# nibblet.net
KiCad netlist of a schematic drawn in EAGLE
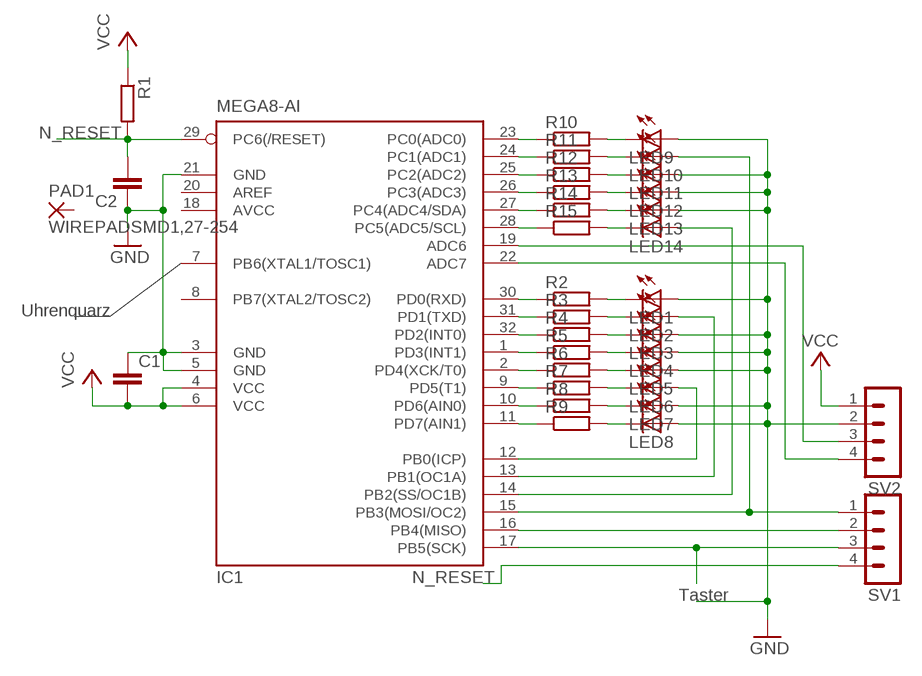
[diagram p0: schematic, sheet 1]

(export (version "E")
  (design (tool "Eeschema 10.0.6"))
  (components
    (comp (ref "C1")
      (value "C-EUC1206")
      (footprint "eagle-import:C1206")
      (libsource (lib "eagle-import") (part "C-EUC1206"))
    )
    (comp (ref "C2")
      (value "C-EUC1206")
      (footprint "eagle-import:C1206")
      (libsource (lib "eagle-import") (part "C-EUC1206"))
    )
    (comp (ref "IC1")
      (value "MEGA8-AI")
      (footprint "eagle-import:TQFP32-08")
      (libsource (lib "eagle-import") (part "MEGA8-AI"))
    )
    (comp (ref "LED1")
      (value "LEDCHIP-LED0805")
      (footprint "eagle-import:CHIP-LED0805")
      (libsource (lib "eagle-import") (part "LEDCHIP-LED0805"))
    )
    (comp (ref "LED2")
      (value "LEDCHIP-LED0805")
      (footprint "eagle-import:CHIP-LED0805")
      (libsource (lib "eagle-import") (part "LEDCHIP-LED0805"))
    )
    (comp (ref "LED3")
      (value "LEDCHIP-LED0805")
      (footprint "eagle-import:CHIP-LED0805")
      (libsource (lib "eagle-import") (part "LEDCHIP-LED0805"))
    )
    (comp (ref "LED4")
      (value "LEDCHIP-LED0805")
      (footprint "eagle-import:CHIP-LED0805")
      (libsource (lib "eagle-import") (part "LEDCHIP-LED0805"))
    )
    (comp (ref "LED5")
      (value "LEDCHIP-LED0805")
      (footprint "eagle-import:CHIP-LED0805")
      (libsource (lib "eagle-import") (part "LEDCHIP-LED0805"))
    )
    (comp (ref "LED6")
      (value "LEDCHIP-LED0805")
      (footprint "eagle-import:CHIP-LED0805")
      (libsource (lib "eagle-import") (part "LEDCHIP-LED0805"))
    )
    (comp (ref "LED7")
      (value "LEDCHIP-LED0805")
      (footprint "eagle-import:CHIP-LED0805")
      (libsource (lib "eagle-import") (part "LEDCHIP-LED0805"))
    )
    (comp (ref "LED8")
      (value "LEDCHIP-LED0805")
      (footprint "eagle-import:CHIP-LED0805")
      (libsource (lib "eagle-import") (part "LEDCHIP-LED0805"))
    )
    (comp (ref "LED9")
      (value "LEDCHIP-LED0805")
      (footprint "eagle-import:CHIP-LED0805")
      (libsource (lib "eagle-import") (part "LEDCHIP-LED0805"))
    )
    (comp (ref "LED10")
      (value "LEDCHIP-LED0805")
      (footprint "eagle-import:CHIP-LED0805")
      (libsource (lib "eagle-import") (part "LEDCHIP-LED0805"))
    )
    (comp (ref "LED11")
      (value "LEDCHIP-LED0805")
      (footprint "eagle-import:CHIP-LED0805")
      (libsource (lib "eagle-import") (part "LEDCHIP-LED0805"))
    )
    (comp (ref "LED12")
      (value "LEDCHIP-LED0805")
      (footprint "eagle-import:CHIP-LED0805")
      (libsource (lib "eagle-import") (part "LEDCHIP-LED0805"))
    )
    (comp (ref "LED13")
      (value "LEDCHIP-LED0805")
      (footprint "eagle-import:CHIP-LED0805")
      (libsource (lib "eagle-import") (part "LEDCHIP-LED0805"))
    )
    (comp (ref "LED14")
      (value "LEDCHIP-LED0805")
      (footprint "eagle-import:CHIP-LED0805")
      (libsource (lib "eagle-import") (part "LEDCHIP-LED0805"))
    )
    (comp (ref "PAD1")
      (value "WIREPADSMD1,27-254")
      (footprint "eagle-import:SMD1,27-2,54")
      (libsource (lib "eagle-import") (part "WIREPADSMD1,27-254"))
    )
    (comp (ref "R1")
      (value "R-EU_M1206")
      (footprint "eagle-import:M1206")
      (libsource (lib "eagle-import") (part "R-EU_M1206"))
    )
    (comp (ref "R2")
      (value "R-EU_R0805")
      (footprint "eagle-import:R0805")
      (libsource (lib "eagle-import") (part "R-EU_R0805"))
    )
    (comp (ref "R3")
      (value "R-EU_R0805")
      (footprint "eagle-import:R0805")
      (libsource (lib "eagle-import") (part "R-EU_R0805"))
    )
    (comp (ref "R4")
      (value "R-EU_R0805")
      (footprint "eagle-import:R0805")
      (libsource (lib "eagle-import") (part "R-EU_R0805"))
    )
    (comp (ref "R5")
      (value "R-EU_R0805")
      (footprint "eagle-import:R0805")
      (libsource (lib "eagle-import") (part "R-EU_R0805"))
    )
    (comp (ref "R6")
      (value "R-EU_R0805")
      (footprint "eagle-import:R0805")
      (libsource (lib "eagle-import") (part "R-EU_R0805"))
    )
    (comp (ref "R7")
      (value "R-EU_R0805")
      (footprint "eagle-import:R0805")
      (libsource (lib "eagle-import") (part "R-EU_R0805"))
    )
    (comp (ref "R8")
      (value "R-EU_R0805")
      (footprint "eagle-import:R0805")
      (libsource (lib "eagle-import") (part "R-EU_R0805"))
    )
    (comp (ref "R9")
      (value "R-EU_R0805")
      (footprint "eagle-import:R0805")
      (libsource (lib "eagle-import") (part "R-EU_R0805"))
    )
    (comp (ref "R10")
      (value "R-EU_R0805")
      (footprint "eagle-import:R0805")
      (libsource (lib "eagle-import") (part "R-EU_R0805"))
    )
    (comp (ref "R11")
      (value "R-EU_R0805")
      (footprint "eagle-import:R0805")
      (libsource (lib "eagle-import") (part "R-EU_R0805"))
    )
    (comp (ref "R12")
      (value "R-EU_R0805")
      (footprint "eagle-import:R0805")
      (libsource (lib "eagle-import") (part "R-EU_R0805"))
    )
    (comp (ref "R13")
      (value "R-EU_R0805")
      (footprint "eagle-import:R0805")
      (libsource (lib "eagle-import") (part "R-EU_R0805"))
    )
    (comp (ref "R14")
      (value "R-EU_R0805")
      (footprint "eagle-import:R0805")
      (libsource (lib "eagle-import") (part "R-EU_R0805"))
    )
    (comp (ref "R15")
      (value "R-EU_R0805")
      (footprint "eagle-import:R0805")
      (libsource (lib "eagle-import") (part "R-EU_R0805"))
    )
    (comp (ref "SV1")
      (value "MA04-1")
      (footprint "eagle-import:MA04-1")
      (libsource (lib "eagle-import") (part "MA04-1"))
    )
    (comp (ref "SV2")
      (value "MA04-1")
      (footprint "eagle-import:MA04-1")
      (libsource (lib "eagle-import") (part "MA04-1"))
    )
  )
  (nets
    (net (code "1") (name "/AVCC") (class "Default")
      (node (ref "IC1") (pin "18") (pinfunction "AVCC_18") (pintype "power_in"))
    )
    (net (code "2") (name "/N_RESET") (class "Default")
      (node (ref "C2") (pin "2") (pinfunction "2_2") (pintype "passive"))
      (node (ref "IC1") (pin "29") (pinfunction "PC6(/RESET)_29") (pintype "bidirectional"))
      (node (ref "R1") (pin "2") (pinfunction "2_2") (pintype "passive"))
      (node (ref "SV1") (pin "4") (pinfunction "4_4") (pintype "passive"))
    )
    (net (code "3") (name "GND") (class "Default")
      (node (ref "C1") (pin "1") (pinfunction "1_1") (pintype "passive"))
      (node (ref "C2") (pin "1") (pinfunction "1_1") (pintype "passive"))
      (node (ref "IC1") (pin "21") (pinfunction "GND_21") (pintype "power_in"))
      (node (ref "IC1") (pin "3") (pinfunction "GND_3") (pintype "power_in"))
      (node (ref "IC1") (pin "5") (pinfunction "GND_5") (pintype "power_in"))
      (node (ref "LED1") (pin "A") (pinfunction "A_A") (pintype "passive"))
      (node (ref "LED11") (pin "A") (pinfunction "A_A") (pintype "passive"))
      (node (ref "LED12") (pin "A") (pinfunction "A_A") (pintype "passive"))
      (node (ref "LED13") (pin "A") (pinfunction "A_A") (pintype "passive"))
      (node (ref "LED3") (pin "A") (pinfunction "A_A") (pintype "passive"))
      (node (ref "LED4") (pin "A") (pinfunction "A_A") (pintype "passive"))
      (node (ref "LED5") (pin "A") (pinfunction "A_A") (pintype "passive"))
      (node (ref "LED7") (pin "A") (pinfunction "A_A") (pintype "passive"))
      (node (ref "LED8") (pin "A") (pinfunction "A_A") (pintype "passive"))
      (node (ref "LED9") (pin "A") (pinfunction "A_A") (pintype "passive"))
      (node (ref "SV2") (pin "2") (pinfunction "2_2") (pintype "passive"))
    )
    (net (code "4") (name "Net-(IC1-ADC6)") (class "Default")
      (node (ref "IC1") (pin "19") (pinfunction "ADC6_19") (pintype "bidirectional"))
      (node (ref "SV2") (pin "3") (pinfunction "3_3") (pintype "passive"))
    )
    (net (code "5") (name "Net-(IC1-ADC7)") (class "Default")
      (node (ref "IC1") (pin "22") (pinfunction "ADC7_22") (pintype "bidirectional"))
      (node (ref "SV2") (pin "4") (pinfunction "4_4") (pintype "passive"))
    )
    (net (code "6") (name "Net-(IC1-PB0(ICP))") (class "Default")
      (node (ref "IC1") (pin "12") (pinfunction "PB0(ICP)_12") (pintype "bidirectional"))
      (node (ref "LED6") (pin "A") (pinfunction "A_A") (pintype "passive"))
    )
    (net (code "7") (name "Net-(IC1-PB1(OC1A))") (class "Default")
      (node (ref "IC1") (pin "13") (pinfunction "PB1(OC1A)_13") (pintype "bidirectional"))
      (node (ref "LED2") (pin "A") (pinfunction "A_A") (pintype "passive"))
    )
    (net (code "8") (name "Net-(IC1-PB2(SS{slash}OC1B))") (class "Default")
      (node (ref "IC1") (pin "14") (pinfunction "PB2(SS/OC1B)_14") (pintype "bidirectional"))
      (node (ref "LED14") (pin "A") (pinfunction "A_A") (pintype "passive"))
    )
    (net (code "9") (name "Net-(IC1-PB3(MOSI{slash}OC2))") (class "Default")
      (node (ref "IC1") (pin "15") (pinfunction "PB3(MOSI/OC2)_15") (pintype "bidirectional"))
      (node (ref "LED10") (pin "A") (pinfunction "A_A") (pintype "passive"))
      (node (ref "SV1") (pin "1") (pinfunction "1_1") (pintype "passive"))
    )
    (net (code "10") (name "Net-(IC1-PB4(MISO))") (class "Default")
      (node (ref "IC1") (pin "16") (pinfunction "PB4(MISO)_16") (pintype "bidirectional"))
      (node (ref "SV1") (pin "2") (pinfunction "2_2") (pintype "passive"))
    )
    (net (code "11") (name "Net-(IC1-PB5(SCK))") (class "Default")
      (node (ref "IC1") (pin "17") (pinfunction "PB5(SCK)_17") (pintype "bidirectional"))
      (node (ref "SV1") (pin "3") (pinfunction "3_3") (pintype "passive"))
    )
    (net (code "12") (name "Net-(IC1-PC0(ADC0))") (class "Default")
      (node (ref "IC1") (pin "23") (pinfunction "PC0(ADC0)_23") (pintype "bidirectional"))
      (node (ref "R10") (pin "1") (pinfunction "1_1") (pintype "passive"))
    )
    (net (code "13") (name "Net-(IC1-PC1(ADC1))") (class "Default")
      (node (ref "IC1") (pin "24") (pinfunction "PC1(ADC1)_24") (pintype "bidirectional"))
      (node (ref "R11") (pin "1") (pinfunction "1_1") (pintype "passive"))
    )
    (net (code "14") (name "Net-(IC1-PC2(ADC2))") (class "Default")
      (node (ref "IC1") (pin "25") (pinfunction "PC2(ADC2)_25") (pintype "bidirectional"))
      (node (ref "R12") (pin "1") (pinfunction "1_1") (pintype "passive"))
    )
    (net (code "15") (name "Net-(IC1-PC3(ADC3))") (class "Default")
      (node (ref "IC1") (pin "26") (pinfunction "PC3(ADC3)_26") (pintype "bidirectional"))
      (node (ref "R13") (pin "1") (pinfunction "1_1") (pintype "passive"))
    )
    (net (code "16") (name "Net-(IC1-PC4(ADC4{slash}SDA))") (class "Default")
      (node (ref "IC1") (pin "27") (pinfunction "PC4(ADC4/SDA)_27") (pintype "bidirectional"))
      (node (ref "R14") (pin "1") (pinfunction "1_1") (pintype "passive"))
    )
    (net (code "17") (name "Net-(IC1-PC5(ADC5{slash}SCL))") (class "Default")
      (node (ref "IC1") (pin "28") (pinfunction "PC5(ADC5/SCL)_28") (pintype "bidirectional"))
      (node (ref "R15") (pin "1") (pinfunction "1_1") (pintype "passive"))
    )
    (net (code "18") (name "Net-(IC1-PD0(RXD))") (class "Default")
      (node (ref "IC1") (pin "30") (pinfunction "PD0(RXD)_30") (pintype "bidirectional"))
      (node (ref "R2") (pin "1") (pinfunction "1_1") (pintype "passive"))
    )
    (net (code "19") (name "Net-(IC1-PD1(TXD))") (class "Default")
      (node (ref "IC1") (pin "31") (pinfunction "PD1(TXD)_31") (pintype "bidirectional"))
      (node (ref "R3") (pin "1") (pinfunction "1_1") (pintype "passive"))
    )
    (net (code "20") (name "Net-(IC1-PD2(INT0))") (class "Default")
      (node (ref "IC1") (pin "32") (pinfunction "PD2(INT0)_32") (pintype "bidirectional"))
      (node (ref "R4") (pin "1") (pinfunction "1_1") (pintype "passive"))
    )
    (net (code "21") (name "Net-(IC1-PD3(INT1))") (class "Default")
      (node (ref "IC1") (pin "1") (pinfunction "PD3(INT1)_1") (pintype "bidirectional"))
      (node (ref "R5") (pin "1") (pinfunction "1_1") (pintype "passive"))
    )
    (net (code "22") (name "Net-(IC1-PD4(XCK{slash}T0))") (class "Default")
      (node (ref "IC1") (pin "2") (pinfunction "PD4(XCK/T0)_2") (pintype "bidirectional"))
      (node (ref "R6") (pin "1") (pinfunction "1_1") (pintype "passive"))
    )
    (net (code "23") (name "Net-(IC1-PD5(T1))") (class "Default")
      (node (ref "IC1") (pin "9") (pinfunction "PD5(T1)_9") (pintype "bidirectional"))
      (node (ref "R7") (pin "1") (pinfunction "1_1") (pintype "passive"))
    )
    (net (code "24") (name "Net-(IC1-PD6(AIN0))") (class "Default")
      (node (ref "IC1") (pin "10") (pinfunction "PD6(AIN0)_10") (pintype "bidirectional"))
      (node (ref "R8") (pin "1") (pinfunction "1_1") (pintype "passive"))
    )
    (net (code "25") (name "Net-(IC1-PD7(AIN1))") (class "Default")
      (node (ref "IC1") (pin "11") (pinfunction "PD7(AIN1)_11") (pintype "bidirectional"))
      (node (ref "R9") (pin "1") (pinfunction "1_1") (pintype "passive"))
    )
    (net (code "26") (name "Net-(LED1-PadC)") (class "Default")
      (node (ref "LED1") (pin "C") (pinfunction "C_C") (pintype "passive"))
      (node (ref "R2") (pin "2") (pinfunction "2_2") (pintype "passive"))
    )
    (net (code "27") (name "Net-(LED2-PadC)") (class "Default")
      (node (ref "LED2") (pin "C") (pinfunction "C_C") (pintype "passive"))
      (node (ref "R3") (pin "2") (pinfunction "2_2") (pintype "passive"))
    )
    (net (code "28") (name "Net-(LED3-PadC)") (class "Default")
      (node (ref "LED3") (pin "C") (pinfunction "C_C") (pintype "passive"))
      (node (ref "R4") (pin "2") (pinfunction "2_2") (pintype "passive"))
    )
    (net (code "29") (name "Net-(LED4-PadC)") (class "Default")
      (node (ref "LED4") (pin "C") (pinfunction "C_C") (pintype "passive"))
      (node (ref "R5") (pin "2") (pinfunction "2_2") (pintype "passive"))
    )
    (net (code "30") (name "Net-(LED5-PadC)") (class "Default")
      (node (ref "LED5") (pin "C") (pinfunction "C_C") (pintype "passive"))
      (node (ref "R6") (pin "2") (pinfunction "2_2") (pintype "passive"))
    )
    (net (code "31") (name "Net-(LED6-PadC)") (class "Default")
      (node (ref "LED6") (pin "C") (pinfunction "C_C") (pintype "passive"))
      (node (ref "R7") (pin "2") (pinfunction "2_2") (pintype "passive"))
    )
    (net (code "32") (name "Net-(LED7-PadC)") (class "Default")
      (node (ref "LED7") (pin "C") (pinfunction "C_C") (pintype "passive"))
      (node (ref "R8") (pin "2") (pinfunction "2_2") (pintype "passive"))
    )
    (net (code "33") (name "Net-(LED8-PadC)") (class "Default")
      (node (ref "LED8") (pin "C") (pinfunction "C_C") (pintype "passive"))
      (node (ref "R9") (pin "2") (pinfunction "2_2") (pintype "passive"))
    )
    (net (code "34") (name "Net-(LED9-PadC)") (class "Default")
      (node (ref "LED9") (pin "C") (pinfunction "C_C") (pintype "passive"))
      (node (ref "R10") (pin "2") (pinfunction "2_2") (pintype "passive"))
    )
    (net (code "35") (name "Net-(LED10-PadC)") (class "Default")
      (node (ref "LED10") (pin "C") (pinfunction "C_C") (pintype "passive"))
      (node (ref "R11") (pin "2") (pinfunction "2_2") (pintype "passive"))
    )
    (net (code "36") (name "Net-(LED11-PadC)") (class "Default")
      (node (ref "LED11") (pin "C") (pinfunction "C_C") (pintype "passive"))
      (node (ref "R12") (pin "2") (pinfunction "2_2") (pintype "passive"))
    )
    (net (code "37") (name "Net-(LED12-PadC)") (class "Default")
      (node (ref "LED12") (pin "C") (pinfunction "C_C") (pintype "passive"))
      (node (ref "R13") (pin "2") (pinfunction "2_2") (pintype "passive"))
    )
    (net (code "38") (name "Net-(LED13-PadC)") (class "Default")
      (node (ref "LED13") (pin "C") (pinfunction "C_C") (pintype "passive"))
      (node (ref "R14") (pin "2") (pinfunction "2_2") (pintype "passive"))
    )
    (net (code "39") (name "Net-(LED14-PadC)") (class "Default")
      (node (ref "LED14") (pin "C") (pinfunction "C_C") (pintype "passive"))
      (node (ref "R15") (pin "2") (pinfunction "2_2") (pintype "passive"))
    )
    (net (code "40") (name "VCC") (class "Default")
      (node (ref "C1") (pin "2") (pinfunction "2_2") (pintype "passive"))
      (node (ref "IC1") (pin "4") (pinfunction "VCC_4") (pintype "power_in"))
      (node (ref "IC1") (pin "6") (pinfunction "VCC_6") (pintype "power_in"))
      (node (ref "R1") (pin "1") (pinfunction "1_1") (pintype "passive"))
      (node (ref "SV2") (pin "1") (pinfunction "1_1") (pintype "passive"))
    )
    (net (code "41") (name "unconnected-(IC1-AREF-Pad20)") (class "Default")
      (node (ref "IC1") (pin "20") (pinfunction "AREF_20") (pintype "passive"))
    )
    (net (code "42") (name "unconnected-(IC1-PB6(XTAL1{slash}TOSC1)-Pad7)") (class "Default")
      (node (ref "IC1") (pin "7") (pinfunction "PB6(XTAL1/TOSC1)_7") (pintype "bidirectional"))
    )
    (net (code "43") (name "unconnected-(IC1-PB7(XTAL2{slash}TOSC2)-Pad8)") (class "Default")
      (node (ref "IC1") (pin "8") (pinfunction "PB7(XTAL2/TOSC2)_8") (pintype "bidirectional"))
    )
    (net (code "44") (name "unconnected-(PAD1-P-Pad1)") (class "Default")
      (node (ref "PAD1") (pin "1") (pinfunction "P_1") (pintype "passive"))
    )
  )
)
